# USB-UART.net
KiCad netlist of a schematic drawn in Altium Designer
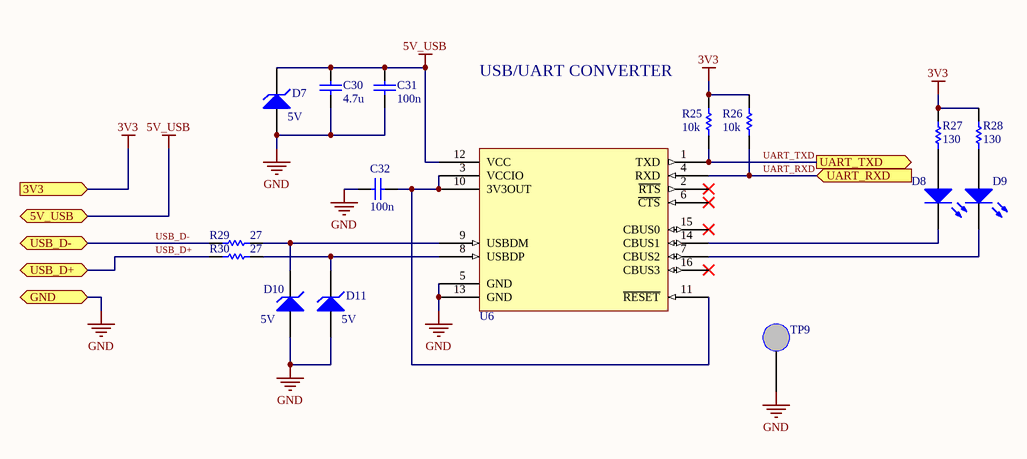
[diagram p0: USB-UART.SchDoc]

(export (version "E")
  (design (tool "Eeschema 10.0.6"))
  (components
    (comp (ref "C30")
      (value "4.7u")
      (footprint "CS-0603")
      (fields
        (field (name "TOLERANCE") "10%")
        (field (name "VOLTAGE") "16V")
        (field (name "Comment") "CS - CAPACITOR")
      )
      (libsource (lib "CHINOOK_LIBRARY") (part "CS - CAPACITOR"))
    )
    (comp (ref "C31")
      (value "100n")
      (footprint "CS-0603")
      (fields
        (field (name "TOLERANCE") "10%")
        (field (name "VOLTAGE") "16V")
        (field (name "Comment") "CS - CAPACITOR")
      )
      (libsource (lib "CHINOOK_LIBRARY") (part "CS - CAPACITOR"))
    )
    (comp (ref "C32")
      (value "100n")
      (footprint "CS-0603")
      (fields
        (field (name "TOLERANCE") "10%")
        (field (name "VOLTAGE") "16V")
        (field (name "Comment") "CS - CAPACITOR")
      )
      (libsource (lib "CHINOOK_LIBRARY") (part "CS - CAPACITOR"))
    )
    (comp (ref "D7")
      (value "DS - TVS ESD5Z5.0T1G")
      (footprint "DS-SOD523")
      (description "TVS 5V")
      (fields
        (field (name "MANUFACTURER") "ON Semiconductor")
        (field (name "VOLTAGE - REVERSE STANDOFF (TYP)") "5V")
      )
      (libsource (lib "CHINOOK_LIBRARY") (part "DS - TVS ESD5Z5.0T1G"))
    )
    (comp (ref "D8")
      (value "LED - NORMAL LED")
      (footprint "LED-0603 GREEN")
      (libsource (lib "CHINOOK_LIBRARY") (part "LED - NORMAL LED"))
    )
    (comp (ref "D9")
      (value "LED - NORMAL LED")
      (footprint "LED-0603 GREEN")
      (libsource (lib "CHINOOK_LIBRARY") (part "LED - NORMAL LED"))
    )
    (comp (ref "D10")
      (value "DS - TVS ESD5Z5.0T1G")
      (footprint "DS-SOD523")
      (description "TVS 5V")
      (fields
        (field (name "MANUFACTURER") "ON Semiconductor")
        (field (name "VOLTAGE - REVERSE STANDOFF (TYP)") "5V")
      )
      (libsource (lib "CHINOOK_LIBRARY") (part "DS - TVS ESD5Z5.0T1G"))
    )
    (comp (ref "D11")
      (value "DS - TVS ESD5Z5.0T1G")
      (footprint "DS-SOD523")
      (description "TVS 5V")
      (fields
        (field (name "MANUFACTURER") "ON Semiconductor")
        (field (name "VOLTAGE - REVERSE STANDOFF (TYP)") "5V")
      )
      (libsource (lib "CHINOOK_LIBRARY") (part "DS - TVS ESD5Z5.0T1G"))
    )
    (comp (ref "R25")
      (value "10k")
      (footprint "RS-0603")
      (fields
        (field (name "TOLERANCE") "RES TOL")
        (field (name "POWER") "RES POWER")
        (field (name "Comment") "RS - RESISTOR")
      )
      (libsource (lib "CHINOOK_LIBRARY") (part "RS - RESISTOR"))
    )
    (comp (ref "R26")
      (value "10k")
      (footprint "RS-0603")
      (fields
        (field (name "TOLERANCE") "RES TOL")
        (field (name "POWER") "RES POWER")
        (field (name "Comment") "RS - RESISTOR")
      )
      (libsource (lib "CHINOOK_LIBRARY") (part "RS - RESISTOR"))
    )
    (comp (ref "R27")
      (value "130")
      (footprint "RS-0603")
      (fields
        (field (name "TOLERANCE") "RES TOL")
        (field (name "POWER") "RES POWER")
        (field (name "Comment") "RS - RESISTOR")
      )
      (libsource (lib "CHINOOK_LIBRARY") (part "RS - RESISTOR"))
    )
    (comp (ref "R28")
      (value "130")
      (footprint "RS-0603")
      (fields
        (field (name "TOLERANCE") "RES TOL")
        (field (name "POWER") "RES POWER")
        (field (name "Comment") "RS - RESISTOR")
      )
      (libsource (lib "CHINOOK_LIBRARY") (part "RS - RESISTOR"))
    )
    (comp (ref "R29")
      (value "27")
      (footprint "RS-0603")
      (fields
        (field (name "TOLERANCE") "RES TOL")
        (field (name "POWER") "RES POWER")
        (field (name "Comment") "RS - RESISTOR")
      )
      (libsource (lib "CHINOOK_LIBRARY") (part "RS - RESISTOR"))
    )
    (comp (ref "R30")
      (value "27")
      (footprint "RS-0603")
      (fields
        (field (name "TOLERANCE") "RES TOL")
        (field (name "POWER") "RES POWER")
        (field (name "Comment") "RS - RESISTOR")
      )
      (libsource (lib "CHINOOK_LIBRARY") (part "RS - RESISTOR"))
    )
    (comp (ref "TP9")
      (value "5003K")
      (footprint "TP - VERTICAL")
      (libsource (lib "CHINOOK_LIBRARY") (part "TP - Test point vertical"))
    )
    (comp (ref "U6")
      (value "IC - FT230XS")
      (footprint "IC-SSOP-16")
      (description "USB to BASIC UART IC")
      (fields (field (name "MANUFACTURER") "FTDI"))
      (libsource (lib "CHINOOK_LIBRARY") (part "IC - FT230XS"))
    )
  )
  (nets
    (net (code "1") (name "/UART_RXD") (class "Default")
      (node (ref "R26") (pin "1") (pinfunction "1_1") (pintype "passive"))
      (node (ref "U6") (pin "4") (pinfunction "RXD_4") (pintype "input"))
    )
    (net (code "2") (name "/UART_TXD") (class "Default")
      (node (ref "R25") (pin "1") (pinfunction "1_1") (pintype "passive"))
      (node (ref "U6") (pin "1") (pinfunction "TXD_1") (pintype "output"))
    )
    (net (code "3") (name "/USB_D+") (class "Default")
      (node (ref "R30") (pin "2") (pinfunction "2_2") (pintype "passive"))
    )
    (net (code "4") (name "/USB_D-") (class "Default")
      (node (ref "R29") (pin "2") (pinfunction "2_2") (pintype "passive"))
    )
    (net (code "5") (name "3V3") (class "Default")
      (node (ref "R25") (pin "2") (pinfunction "2_2") (pintype "passive"))
      (node (ref "R26") (pin "2") (pinfunction "2_2") (pintype "passive"))
      (node (ref "R27") (pin "2") (pinfunction "2_2") (pintype "passive"))
      (node (ref "R28") (pin "2") (pinfunction "2_2") (pintype "passive"))
    )
    (net (code "6") (name "5V_USB") (class "Default")
      (node (ref "C30") (pin "2") (pinfunction "2_2") (pintype "passive"))
      (node (ref "C31") (pin "2") (pinfunction "2_2") (pintype "passive"))
      (node (ref "D7") (pin "K") (pinfunction "K_K") (pintype "passive"))
      (node (ref "U6") (pin "12") (pinfunction "VCC_12") (pintype "power_in"))
    )
    (net (code "7") (name "GND") (class "Default")
      (node (ref "C30") (pin "1") (pinfunction "1_1") (pintype "passive"))
      (node (ref "C31") (pin "1") (pinfunction "1_1") (pintype "passive"))
      (node (ref "C32") (pin "2") (pinfunction "2_2") (pintype "passive"))
      (node (ref "D10") (pin "A") (pinfunction "A_A") (pintype "passive"))
      (node (ref "D11") (pin "A") (pinfunction "A_A") (pintype "passive"))
      (node (ref "D7") (pin "A") (pinfunction "A_A") (pintype "passive"))
      (node (ref "TP9") (pin "1") (pinfunction "1_1") (pintype "passive"))
      (node (ref "U6") (pin "13") (pinfunction "GND_13") (pintype "power_in"))
      (node (ref "U6") (pin "5") (pinfunction "GND_5") (pintype "power_in"))
    )
    (net (code "8") (name "Net-(D8-PadA)") (class "Default")
      (node (ref "D8") (pin "A") (pinfunction "A_A") (pintype "passive"))
      (node (ref "R27") (pin "1") (pinfunction "1_1") (pintype "passive"))
    )
    (net (code "9") (name "Net-(D9-PadA)") (class "Default")
      (node (ref "D9") (pin "A") (pinfunction "A_A") (pintype "passive"))
      (node (ref "R28") (pin "1") (pinfunction "1_1") (pintype "passive"))
    )
    (net (code "10") (name "Net-(U6-3V3OUT)") (class "Default")
      (node (ref "C32") (pin "1") (pinfunction "1_1") (pintype "passive"))
      (node (ref "U6") (pin "10") (pinfunction "3V3OUT_10") (pintype "power_in"))
      (node (ref "U6") (pin "11") (pinfunction "~{RESET}_11") (pintype "input"))
      (node (ref "U6") (pin "3") (pinfunction "VCCIO_3") (pintype "power_in"))
    )
    (net (code "11") (name "Net-(U6-CBUS1)") (class "Default")
      (node (ref "D8") (pin "K") (pinfunction "K_K") (pintype "passive"))
      (node (ref "U6") (pin "14") (pinfunction "CBUS1_14") (pintype "bidirectional"))
    )
    (net (code "12") (name "Net-(U6-CBUS2)") (class "Default")
      (node (ref "D9") (pin "K") (pinfunction "K_K") (pintype "passive"))
      (node (ref "U6") (pin "7") (pinfunction "CBUS2_7") (pintype "bidirectional"))
    )
    (net (code "13") (name "Net-(U6-USBDM)") (class "Default")
      (node (ref "D10") (pin "K") (pinfunction "K_K") (pintype "passive"))
      (node (ref "R29") (pin "1") (pinfunction "1_1") (pintype "passive"))
      (node (ref "U6") (pin "9") (pinfunction "USBDM_9") (pintype "input"))
    )
    (net (code "14") (name "Net-(U6-USBDP)") (class "Default")
      (node (ref "D11") (pin "K") (pinfunction "K_K") (pintype "passive"))
      (node (ref "R30") (pin "1") (pinfunction "1_1") (pintype "passive"))
      (node (ref "U6") (pin "8") (pinfunction "USBDP_8") (pintype "input"))
    )
    (net (code "15") (name "unconnected-(U6-CBUS0-Pad15)") (class "Default")
      (node (ref "U6") (pin "15") (pinfunction "CBUS0_15") (pintype "bidirectional+no_connect"))
    )
    (net (code "16") (name "unconnected-(U6-CBUS3-Pad16)") (class "Default")
      (node (ref "U6") (pin "16") (pinfunction "CBUS3_16") (pintype "bidirectional+no_connect"))
    )
    (net (code "17") (name "unconnected-(U6-~{CTS}-Pad6)") (class "Default")
      (node (ref "U6") (pin "6") (pinfunction "~{CTS}_6") (pintype "input+no_connect"))
    )
    (net (code "18") (name "unconnected-(U6-~{RTS}-Pad2)") (class "Default")
      (node (ref "U6") (pin "2") (pinfunction "~{RTS}_2") (pintype "output+no_connect"))
    )
  )
)
